# PicoZed.net
KiCad netlist of a schematic drawn in Altium Designer
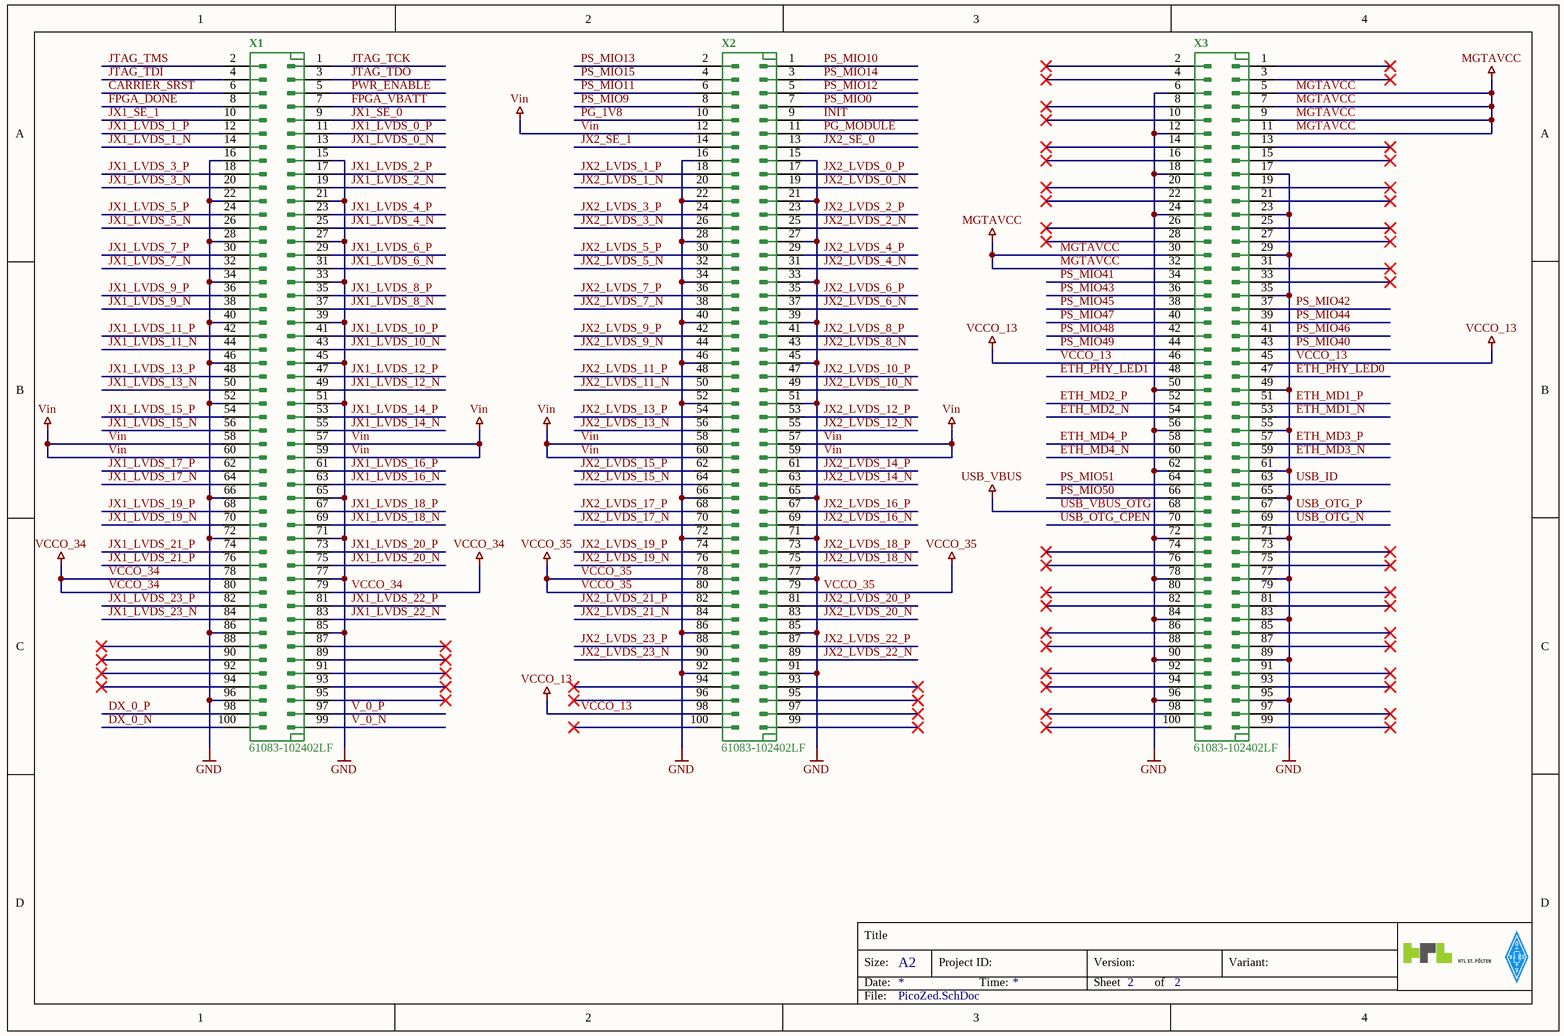
[diagram p0: PicoZed.SchDoc]

(export (version "E")
  (design (tool "Eeschema 10.0.6"))
  (components
    (comp (ref "X1")
      (value "61083-102402LF")
      (footprint "PrometheusLib:61083-102402LF")
      (libsource (lib "PrometheusLib") (part "X_61083-102402LF"))
    )
    (comp (ref "X2")
      (value "61083-102402LF")
      (footprint "PrometheusLib:61083-102402LF")
      (libsource (lib "PrometheusLib") (part "X_61083-102402LF"))
    )
    (comp (ref "X3")
      (value "61083-102402LF")
      (footprint "PrometheusLib:61083-102402LF")
      (libsource (lib "PrometheusLib") (part "X_61083-102402LF"))
    )
  )
  (nets
    (net (code "1") (name "/DX_0_N") (class "Default")
      (node (ref "X1") (pin "100") (pinfunction "100_100") (pintype "passive"))
    )
    (net (code "2") (name "/DX_0_P") (class "Default")
      (node (ref "X1") (pin "98") (pinfunction "98_98") (pintype "passive"))
    )
    (net (code "3") (name "/ETH_MD1_N") (class "Default")
      (node (ref "X3") (pin "53") (pinfunction "53_53") (pintype "passive"))
    )
    (net (code "4") (name "/ETH_MD1_P") (class "Default")
      (node (ref "X3") (pin "51") (pinfunction "51_51") (pintype "passive"))
    )
    (net (code "5") (name "/ETH_MD2_N") (class "Default")
      (node (ref "X3") (pin "54") (pinfunction "54_54") (pintype "passive"))
    )
    (net (code "6") (name "/ETH_MD2_P") (class "Default")
      (node (ref "X3") (pin "52") (pinfunction "52_52") (pintype "passive"))
    )
    (net (code "7") (name "/ETH_MD3_N") (class "Default")
      (node (ref "X3") (pin "59") (pinfunction "59_59") (pintype "passive"))
    )
    (net (code "8") (name "/ETH_MD3_P") (class "Default")
      (node (ref "X3") (pin "57") (pinfunction "57_57") (pintype "passive"))
    )
    (net (code "9") (name "/ETH_MD4_N") (class "Default")
      (node (ref "X3") (pin "60") (pinfunction "60_60") (pintype "passive"))
    )
    (net (code "10") (name "/ETH_MD4_P") (class "Default")
      (node (ref "X3") (pin "58") (pinfunction "58_58") (pintype "passive"))
    )
    (net (code "11") (name "/ETH_PHY_LED0") (class "Default")
      (node (ref "X3") (pin "47") (pinfunction "47_47") (pintype "passive"))
    )
    (net (code "12") (name "/ETH_PHY_LED1") (class "Default")
      (node (ref "X3") (pin "48") (pinfunction "48_48") (pintype "passive"))
    )
    (net (code "13") (name "/FPGA_DONE") (class "Default")
      (node (ref "X1") (pin "8") (pinfunction "8_8") (pintype "passive"))
    )
    (net (code "14") (name "/FPGA_VBATT") (class "Default")
      (node (ref "X1") (pin "7") (pinfunction "7_7") (pintype "passive"))
    )
    (net (code "15") (name "/JTAG_TCK") (class "Default")
      (node (ref "X1") (pin "1") (pinfunction "1_1") (pintype "passive"))
    )
    (net (code "16") (name "/JTAG_TDI") (class "Default")
      (node (ref "X1") (pin "4") (pinfunction "4_4") (pintype "passive"))
    )
    (net (code "17") (name "/JTAG_TDO") (class "Default")
      (node (ref "X1") (pin "3") (pinfunction "3_3") (pintype "passive"))
    )
    (net (code "18") (name "/JTAG_TMS") (class "Default")
      (node (ref "X1") (pin "2") (pinfunction "2_2") (pintype "passive"))
    )
    (net (code "19") (name "/JX1_LVDS_0_N") (class "Default")
      (node (ref "X1") (pin "13") (pinfunction "13_13") (pintype "passive"))
    )
    (net (code "20") (name "/JX1_LVDS_0_P") (class "Default")
      (node (ref "X1") (pin "11") (pinfunction "11_11") (pintype "passive"))
    )
    (net (code "21") (name "/JX1_LVDS_1_N") (class "Default")
      (node (ref "X1") (pin "14") (pinfunction "14_14") (pintype "passive"))
    )
    (net (code "22") (name "/JX1_LVDS_1_P") (class "Default")
      (node (ref "X1") (pin "12") (pinfunction "12_12") (pintype "passive"))
    )
    (net (code "23") (name "/JX1_LVDS_2_N") (class "Default")
      (node (ref "X1") (pin "19") (pinfunction "19_19") (pintype "passive"))
    )
    (net (code "24") (name "/JX1_LVDS_2_P") (class "Default")
      (node (ref "X1") (pin "17") (pinfunction "17_17") (pintype "passive"))
    )
    (net (code "25") (name "/JX1_LVDS_3_N") (class "Default")
      (node (ref "X1") (pin "20") (pinfunction "20_20") (pintype "passive"))
    )
    (net (code "26") (name "/JX1_LVDS_3_P") (class "Default")
      (node (ref "X1") (pin "18") (pinfunction "18_18") (pintype "passive"))
    )
    (net (code "27") (name "/JX1_LVDS_4_N") (class "Default")
      (node (ref "X1") (pin "25") (pinfunction "25_25") (pintype "passive"))
    )
    (net (code "28") (name "/JX1_LVDS_4_P") (class "Default")
      (node (ref "X1") (pin "23") (pinfunction "23_23") (pintype "passive"))
    )
    (net (code "29") (name "/JX1_LVDS_5_N") (class "Default")
      (node (ref "X1") (pin "26") (pinfunction "26_26") (pintype "passive"))
    )
    (net (code "30") (name "/JX1_LVDS_5_P") (class "Default")
      (node (ref "X1") (pin "24") (pinfunction "24_24") (pintype "passive"))
    )
    (net (code "31") (name "/JX1_LVDS_6_N") (class "Default")
      (node (ref "X1") (pin "31") (pinfunction "31_31") (pintype "passive"))
    )
    (net (code "32") (name "/JX1_LVDS_6_P") (class "Default")
      (node (ref "X1") (pin "29") (pinfunction "29_29") (pintype "passive"))
    )
    (net (code "33") (name "/JX1_LVDS_7_N") (class "Default")
      (node (ref "X1") (pin "32") (pinfunction "32_32") (pintype "passive"))
    )
    (net (code "34") (name "/JX1_LVDS_7_P") (class "Default")
      (node (ref "X1") (pin "30") (pinfunction "30_30") (pintype "passive"))
    )
    (net (code "35") (name "/JX1_LVDS_8_N") (class "Default")
      (node (ref "X1") (pin "37") (pinfunction "37_37") (pintype "passive"))
    )
    (net (code "36") (name "/JX1_LVDS_8_P") (class "Default")
      (node (ref "X1") (pin "35") (pinfunction "35_35") (pintype "passive"))
    )
    (net (code "37") (name "/JX1_LVDS_9_N") (class "Default")
      (node (ref "X1") (pin "38") (pinfunction "38_38") (pintype "passive"))
    )
    (net (code "38") (name "/JX1_LVDS_9_P") (class "Default")
      (node (ref "X1") (pin "36") (pinfunction "36_36") (pintype "passive"))
    )
    (net (code "39") (name "/JX1_LVDS_10_N") (class "Default")
      (node (ref "X1") (pin "43") (pinfunction "43_43") (pintype "passive"))
    )
    (net (code "40") (name "/JX1_LVDS_10_P") (class "Default")
      (node (ref "X1") (pin "41") (pinfunction "41_41") (pintype "passive"))
    )
    (net (code "41") (name "/JX1_LVDS_11_N") (class "Default")
      (node (ref "X1") (pin "44") (pinfunction "44_44") (pintype "passive"))
    )
    (net (code "42") (name "/JX1_LVDS_11_P") (class "Default")
      (node (ref "X1") (pin "42") (pinfunction "42_42") (pintype "passive"))
    )
    (net (code "43") (name "/JX1_LVDS_12_N") (class "Default")
      (node (ref "X1") (pin "49") (pinfunction "49_49") (pintype "passive"))
    )
    (net (code "44") (name "/JX1_LVDS_12_P") (class "Default")
      (node (ref "X1") (pin "47") (pinfunction "47_47") (pintype "passive"))
    )
    (net (code "45") (name "/JX1_LVDS_13_N") (class "Default")
      (node (ref "X1") (pin "50") (pinfunction "50_50") (pintype "passive"))
    )
    (net (code "46") (name "/JX1_LVDS_13_P") (class "Default")
      (node (ref "X1") (pin "48") (pinfunction "48_48") (pintype "passive"))
    )
    (net (code "47") (name "/JX1_LVDS_14_N") (class "Default")
      (node (ref "X1") (pin "55") (pinfunction "55_55") (pintype "passive"))
    )
    (net (code "48") (name "/JX1_LVDS_14_P") (class "Default")
      (node (ref "X1") (pin "53") (pinfunction "53_53") (pintype "passive"))
    )
    (net (code "49") (name "/JX1_LVDS_15_N") (class "Default")
      (node (ref "X1") (pin "56") (pinfunction "56_56") (pintype "passive"))
    )
    (net (code "50") (name "/JX1_LVDS_15_P") (class "Default")
      (node (ref "X1") (pin "54") (pinfunction "54_54") (pintype "passive"))
    )
    (net (code "51") (name "/JX1_LVDS_16_N") (class "Default")
      (node (ref "X1") (pin "63") (pinfunction "63_63") (pintype "passive"))
    )
    (net (code "52") (name "/JX1_LVDS_16_P") (class "Default")
      (node (ref "X1") (pin "61") (pinfunction "61_61") (pintype "passive"))
    )
    (net (code "53") (name "/JX1_LVDS_17_N") (class "Default")
      (node (ref "X1") (pin "64") (pinfunction "64_64") (pintype "passive"))
    )
    (net (code "54") (name "/JX1_LVDS_17_P") (class "Default")
      (node (ref "X1") (pin "62") (pinfunction "62_62") (pintype "passive"))
    )
    (net (code "55") (name "/JX1_LVDS_18_N") (class "Default")
      (node (ref "X1") (pin "69") (pinfunction "69_69") (pintype "passive"))
    )
    (net (code "56") (name "/JX1_LVDS_18_P") (class "Default")
      (node (ref "X1") (pin "67") (pinfunction "67_67") (pintype "passive"))
    )
    (net (code "57") (name "/JX1_LVDS_19_N") (class "Default")
      (node (ref "X1") (pin "70") (pinfunction "70_70") (pintype "passive"))
    )
    (net (code "58") (name "/JX1_LVDS_19_P") (class "Default")
      (node (ref "X1") (pin "68") (pinfunction "68_68") (pintype "passive"))
    )
    (net (code "59") (name "/JX1_LVDS_20_N") (class "Default")
      (node (ref "X1") (pin "75") (pinfunction "75_75") (pintype "passive"))
    )
    (net (code "60") (name "/JX1_LVDS_20_P") (class "Default")
      (node (ref "X1") (pin "73") (pinfunction "73_73") (pintype "passive"))
    )
    (net (code "61") (name "/JX1_LVDS_21_P") (class "Default")
      (node (ref "X1") (pin "74") (pinfunction "74_74") (pintype "passive"))
      (node (ref "X1") (pin "76") (pinfunction "76_76") (pintype "passive"))
    )
    (net (code "62") (name "/JX1_LVDS_22_N") (class "Default")
      (node (ref "X1") (pin "83") (pinfunction "83_83") (pintype "passive"))
    )
    (net (code "63") (name "/JX1_LVDS_22_P") (class "Default")
      (node (ref "X1") (pin "81") (pinfunction "81_81") (pintype "passive"))
    )
    (net (code "64") (name "/JX1_LVDS_23_N") (class "Default")
      (node (ref "X1") (pin "84") (pinfunction "84_84") (pintype "passive"))
    )
    (net (code "65") (name "/JX1_LVDS_23_P") (class "Default")
      (node (ref "X1") (pin "82") (pinfunction "82_82") (pintype "passive"))
    )
    (net (code "66") (name "/JX1_SE_0") (class "Default")
      (node (ref "X1") (pin "9") (pinfunction "9_9") (pintype "passive"))
    )
    (net (code "67") (name "/JX1_SE_1") (class "Default")
      (node (ref "X1") (pin "10") (pinfunction "10_10") (pintype "passive"))
    )
    (net (code "68") (name "/JX2_LVDS_0_N") (class "Default")
      (node (ref "X2") (pin "19") (pinfunction "19_19") (pintype "passive"))
    )
    (net (code "69") (name "/JX2_LVDS_0_P") (class "Default")
      (node (ref "X2") (pin "17") (pinfunction "17_17") (pintype "passive"))
    )
    (net (code "70") (name "/JX2_LVDS_1_N") (class "Default")
      (node (ref "X2") (pin "20") (pinfunction "20_20") (pintype "passive"))
    )
    (net (code "71") (name "/JX2_LVDS_1_P") (class "Default")
      (node (ref "X2") (pin "18") (pinfunction "18_18") (pintype "passive"))
    )
    (net (code "72") (name "/JX2_LVDS_2_N") (class "Default")
      (node (ref "X2") (pin "25") (pinfunction "25_25") (pintype "passive"))
    )
    (net (code "73") (name "/JX2_LVDS_2_P") (class "Default")
      (node (ref "X2") (pin "23") (pinfunction "23_23") (pintype "passive"))
    )
    (net (code "74") (name "/JX2_LVDS_3_N") (class "Default")
      (node (ref "X2") (pin "26") (pinfunction "26_26") (pintype "passive"))
    )
    (net (code "75") (name "/JX2_LVDS_3_P") (class "Default")
      (node (ref "X2") (pin "24") (pinfunction "24_24") (pintype "passive"))
    )
    (net (code "76") (name "/JX2_LVDS_4_N") (class "Default")
      (node (ref "X2") (pin "31") (pinfunction "31_31") (pintype "passive"))
    )
    (net (code "77") (name "/JX2_LVDS_4_P") (class "Default")
      (node (ref "X2") (pin "29") (pinfunction "29_29") (pintype "passive"))
    )
    (net (code "78") (name "/JX2_LVDS_5_N") (class "Default")
      (node (ref "X2") (pin "32") (pinfunction "32_32") (pintype "passive"))
    )
    (net (code "79") (name "/JX2_LVDS_5_P") (class "Default")
      (node (ref "X2") (pin "30") (pinfunction "30_30") (pintype "passive"))
    )
    (net (code "80") (name "/JX2_LVDS_6_N") (class "Default")
      (node (ref "X2") (pin "37") (pinfunction "37_37") (pintype "passive"))
    )
    (net (code "81") (name "/JX2_LVDS_6_P") (class "Default")
      (node (ref "X2") (pin "35") (pinfunction "35_35") (pintype "passive"))
    )
    (net (code "82") (name "/JX2_LVDS_7_N") (class "Default")
      (node (ref "X2") (pin "38") (pinfunction "38_38") (pintype "passive"))
    )
    (net (code "83") (name "/JX2_LVDS_7_P") (class "Default")
      (node (ref "X2") (pin "36") (pinfunction "36_36") (pintype "passive"))
    )
    (net (code "84") (name "/JX2_LVDS_8_N") (class "Default")
      (node (ref "X2") (pin "43") (pinfunction "43_43") (pintype "passive"))
    )
    (net (code "85") (name "/JX2_LVDS_8_P") (class "Default")
      (node (ref "X2") (pin "41") (pinfunction "41_41") (pintype "passive"))
    )
    (net (code "86") (name "/JX2_LVDS_9_N") (class "Default")
      (node (ref "X2") (pin "44") (pinfunction "44_44") (pintype "passive"))
    )
    (net (code "87") (name "/JX2_LVDS_9_P") (class "Default")
      (node (ref "X2") (pin "42") (pinfunction "42_42") (pintype "passive"))
    )
    (net (code "88") (name "/JX2_LVDS_10_N") (class "Default")
      (node (ref "X2") (pin "49") (pinfunction "49_49") (pintype "passive"))
    )
    (net (code "89") (name "/JX2_LVDS_10_P") (class "Default")
      (node (ref "X2") (pin "47") (pinfunction "47_47") (pintype "passive"))
    )
    (net (code "90") (name "/JX2_LVDS_11_N") (class "Default")
      (node (ref "X2") (pin "50") (pinfunction "50_50") (pintype "passive"))
    )
    (net (code "91") (name "/JX2_LVDS_11_P") (class "Default")
      (node (ref "X2") (pin "48") (pinfunction "48_48") (pintype "passive"))
    )
    (net (code "92") (name "/JX2_LVDS_12_N") (class "Default")
      (node (ref "X2") (pin "55") (pinfunction "55_55") (pintype "passive"))
    )
    (net (code "93") (name "/JX2_LVDS_12_P") (class "Default")
      (node (ref "X2") (pin "53") (pinfunction "53_53") (pintype "passive"))
    )
    (net (code "94") (name "/JX2_LVDS_13_N") (class "Default")
      (node (ref "X2") (pin "56") (pinfunction "56_56") (pintype "passive"))
    )
    (net (code "95") (name "/JX2_LVDS_13_P") (class "Default")
      (node (ref "X2") (pin "54") (pinfunction "54_54") (pintype "passive"))
    )
    (net (code "96") (name "/JX2_LVDS_14_N") (class "Default")
      (node (ref "X2") (pin "63") (pinfunction "63_63") (pintype "passive"))
    )
    (net (code "97") (name "/JX2_LVDS_14_P") (class "Default")
      (node (ref "X2") (pin "61") (pinfunction "61_61") (pintype "passive"))
    )
    (net (code "98") (name "/JX2_LVDS_15_N") (class "Default")
      (node (ref "X2") (pin "64") (pinfunction "64_64") (pintype "passive"))
    )
    (net (code "99") (name "/JX2_LVDS_15_P") (class "Default")
      (node (ref "X2") (pin "62") (pinfunction "62_62") (pintype "passive"))
    )
    (net (code "100") (name "/JX2_LVDS_16_N") (class "Default")
      (node (ref "X2") (pin "69") (pinfunction "69_69") (pintype "passive"))
    )
    (net (code "101") (name "/JX2_LVDS_16_P") (class "Default")
      (node (ref "X2") (pin "67") (pinfunction "67_67") (pintype "passive"))
    )
    (net (code "102") (name "/JX2_LVDS_17_N") (class "Default")
      (node (ref "X2") (pin "70") (pinfunction "70_70") (pintype "passive"))
    )
    (net (code "103") (name "/JX2_LVDS_17_P") (class "Default")
      (node (ref "X2") (pin "68") (pinfunction "68_68") (pintype "passive"))
    )
    (net (code "104") (name "/JX2_LVDS_18_N") (class "Default")
      (node (ref "X2") (pin "75") (pinfunction "75_75") (pintype "passive"))
    )
    (net (code "105") (name "/JX2_LVDS_18_P") (class "Default")
      (node (ref "X2") (pin "73") (pinfunction "73_73") (pintype "passive"))
    )
    (net (code "106") (name "/JX2_LVDS_19_N") (class "Default")
      (node (ref "X2") (pin "76") (pinfunction "76_76") (pintype "passive"))
    )
    (net (code "107") (name "/JX2_LVDS_19_P") (class "Default")
      (node (ref "X2") (pin "74") (pinfunction "74_74") (pintype "passive"))
    )
    (net (code "108") (name "/JX2_LVDS_20_N") (class "Default")
      (node (ref "X2") (pin "83") (pinfunction "83_83") (pintype "passive"))
    )
    (net (code "109") (name "/JX2_LVDS_20_P") (class "Default")
      (node (ref "X2") (pin "81") (pinfunction "81_81") (pintype "passive"))
    )
    (net (code "110") (name "/JX2_LVDS_21_N") (class "Default")
      (node (ref "X2") (pin "84") (pinfunction "84_84") (pintype "passive"))
    )
    (net (code "111") (name "/JX2_LVDS_21_P") (class "Default")
      (node (ref "X2") (pin "82") (pinfunction "82_82") (pintype "passive"))
    )
    (net (code "112") (name "/JX2_LVDS_22_N") (class "Default")
      (node (ref "X2") (pin "89") (pinfunction "89_89") (pintype "passive"))
    )
    (net (code "113") (name "/JX2_LVDS_22_P") (class "Default")
      (node (ref "X2") (pin "87") (pinfunction "87_87") (pintype "passive"))
    )
    (net (code "114") (name "/JX2_LVDS_23_N") (class "Default")
      (node (ref "X2") (pin "90") (pinfunction "90_90") (pintype "passive"))
    )
    (net (code "115") (name "/JX2_LVDS_23_P") (class "Default")
      (node (ref "X2") (pin "88") (pinfunction "88_88") (pintype "passive"))
    )
    (net (code "116") (name "/JX2_SE_0") (class "Default")
      (node (ref "X2") (pin "13") (pinfunction "13_13") (pintype "passive"))
    )
    (net (code "117") (name "/JX2_SE_1") (class "Default")
      (node (ref "X2") (pin "14") (pinfunction "14_14") (pintype "passive"))
    )
    (net (code "118") (name "/PG_1V8") (class "Default")
      (node (ref "X2") (pin "10") (pinfunction "10_10") (pintype "passive"))
    )
    (net (code "119") (name "/PG_MODULE") (class "Default")
      (node (ref "X2") (pin "11") (pinfunction "11_11") (pintype "passive"))
    )
    (net (code "120") (name "/PS_MIO0") (class "Default")
      (node (ref "X2") (pin "7") (pinfunction "7_7") (pintype "passive"))
    )
    (net (code "121") (name "/PS_MIO9") (class "Default")
      (node (ref "X2") (pin "8") (pinfunction "8_8") (pintype "passive"))
    )
    (net (code "122") (name "/PS_MIO10") (class "Default")
      (node (ref "X2") (pin "1") (pinfunction "1_1") (pintype "passive"))
    )
    (net (code "123") (name "/PS_MIO11") (class "Default")
      (node (ref "X2") (pin "6") (pinfunction "6_6") (pintype "passive"))
    )
    (net (code "124") (name "/PS_MIO12") (class "Default")
      (node (ref "X2") (pin "5") (pinfunction "5_5") (pintype "passive"))
    )
    (net (code "125") (name "/PS_MIO13") (class "Default")
      (node (ref "X2") (pin "2") (pinfunction "2_2") (pintype "passive"))
    )
    (net (code "126") (name "/PS_MIO14") (class "Default")
      (node (ref "X2") (pin "3") (pinfunction "3_3") (pintype "passive"))
    )
    (net (code "127") (name "/PS_MIO15") (class "Default")
      (node (ref "X2") (pin "4") (pinfunction "4_4") (pintype "passive"))
    )
    (net (code "128") (name "/PS_MIO40") (class "Default")
      (node (ref "X3") (pin "43") (pinfunction "43_43") (pintype "passive"))
    )
    (net (code "129") (name "/PS_MIO41") (class "Default")
      (node (ref "X3") (pin "34") (pinfunction "34_34") (pintype "passive"))
    )
    (net (code "130") (name "/PS_MIO42") (class "Default")
      (node (ref "X3") (pin "37") (pinfunction "37_37") (pintype "passive"))
    )
    (net (code "131") (name "/PS_MIO43") (class "Default")
      (node (ref "X3") (pin "36") (pinfunction "36_36") (pintype "passive"))
    )
    (net (code "132") (name "/PS_MIO44") (class "Default")
      (node (ref "X3") (pin "39") (pinfunction "39_39") (pintype "passive"))
    )
    (net (code "133") (name "/PS_MIO45") (class "Default")
      (node (ref "X3") (pin "38") (pinfunction "38_38") (pintype "passive"))
    )
    (net (code "134") (name "/PS_MIO46") (class "Default")
      (node (ref "X3") (pin "41") (pinfunction "41_41") (pintype "passive"))
    )
    (net (code "135") (name "/PS_MIO47") (class "Default")
      (node (ref "X3") (pin "40") (pinfunction "40_40") (pintype "passive"))
    )
    (net (code "136") (name "/PS_MIO48") (class "Default")
      (node (ref "X3") (pin "42") (pinfunction "42_42") (pintype "passive"))
    )
    (net (code "137") (name "/PS_MIO49") (class "Default")
      (node (ref "X3") (pin "44") (pinfunction "44_44") (pintype "passive"))
    )
    (net (code "138") (name "/PS_MIO50") (class "Default")
      (node (ref "X3") (pin "66") (pinfunction "66_66") (pintype "passive"))
    )
    (net (code "139") (name "/PS_MIO51") (class "Default")
      (node (ref "X3") (pin "64") (pinfunction "64_64") (pintype "passive"))
    )
    (net (code "140") (name "/PWR_ENABLE") (class "Default")
      (node (ref "X1") (pin "5") (pinfunction "5_5") (pintype "passive"))
    )
    (net (code "141") (name "/USB_ID") (class "Default")
      (node (ref "X3") (pin "63") (pinfunction "63_63") (pintype "passive"))
    )
    (net (code "142") (name "/USB_OTG_CPEN") (class "Default")
      (node (ref "X3") (pin "70") (pinfunction "70_70") (pintype "passive"))
    )
    (net (code "143") (name "/USB_OTG_N") (class "Default")
      (node (ref "X3") (pin "69") (pinfunction "69_69") (pintype "passive"))
    )
    (net (code "144") (name "/USB_OTG_P") (class "Default")
      (node (ref "X3") (pin "67") (pinfunction "67_67") (pintype "passive"))
    )
    (net (code "145") (name "/V_0_N") (class "Default")
      (node (ref "X1") (pin "99") (pinfunction "99_99") (pintype "passive"))
    )
    (net (code "146") (name "/V_0_P") (class "Default")
      (node (ref "X1") (pin "97") (pinfunction "97_97") (pintype "passive"))
    )
    (net (code "147") (name "/~{CARRIER_SRS}T") (class "Default")
      (node (ref "X1") (pin "6") (pinfunction "6_6") (pintype "passive"))
    )
    (net (code "148") (name "/~{INI}T") (class "Default")
      (node (ref "X2") (pin "9") (pinfunction "9_9") (pintype "passive"))
    )
    (net (code "149") (name "GND") (class "Default")
      (node (ref "X1") (pin "15") (pinfunction "15_15") (pintype "passive"))
      (node (ref "X1") (pin "16") (pinfunction "16_16") (pintype "passive"))
      (node (ref "X1") (pin "21") (pinfunction "21_21") (pintype "passive"))
      (node (ref "X1") (pin "22") (pinfunction "22_22") (pintype "passive"))
      (node (ref "X1") (pin "27") (pinfunction "27_27") (pintype "passive"))
      (node (ref "X1") (pin "28") (pinfunction "28_28") (pintype "passive"))
      (node (ref "X1") (pin "33") (pinfunction "33_33") (pintype "passive"))
      (node (ref "X1") (pin "34") (pinfunction "34_34") (pintype "passive"))
      (node (ref "X1") (pin "39") (pinfunction "39_39") (pintype "passive"))
      (node (ref "X1") (pin "40") (pinfunction "40_40") (pintype "passive"))
      (node (ref "X1") (pin "45") (pinfunction "45_45") (pintype "passive"))
      (node (ref "X1") (pin "46") (pinfunction "46_46") (pintype "passive"))
      (node (ref "X1") (pin "51") (pinfunction "51_51") (pintype "passive"))
      (node (ref "X1") (pin "52") (pinfunction "52_52") (pintype "passive"))
      (node (ref "X1") (pin "65") (pinfunction "65_65") (pintype "passive"))
      (node (ref "X1") (pin "66") (pinfunction "66_66") (pintype "passive"))
      (node (ref "X1") (pin "71") (pinfunction "71_71") (pintype "passive"))
      (node (ref "X1") (pin "72") (pinfunction "72_72") (pintype "passive"))
      (node (ref "X1") (pin "77") (pinfunction "77_77") (pintype "passive"))
      (node (ref "X1") (pin "85") (pinfunction "85_85") (pintype "passive"))
      (node (ref "X1") (pin "86") (pinfunction "86_86") (pintype "passive"))
      (node (ref "X1") (pin "96") (pinfunction "96_96") (pintype "passive"))
      (node (ref "X2") (pin "15") (pinfunction "15_15") (pintype "passive"))
      (node (ref "X2") (pin "16") (pinfunction "16_16") (pintype "passive"))
      (node (ref "X2") (pin "21") (pinfunction "21_21") (pintype "passive"))
      (node (ref "X2") (pin "22") (pinfunction "22_22") (pintype "passive"))
      (node (ref "X2") (pin "27") (pinfunction "27_27") (pintype "passive"))
      (node (ref "X2") (pin "28") (pinfunction "28_28") (pintype "passive"))
      (node (ref "X2") (pin "33") (pinfunction "33_33") (pintype "passive"))
      (node (ref "X2") (pin "34") (pinfunction "34_34") (pintype "passive"))
      (node (ref "X2") (pin "39") (pinfunction "39_39") (pintype "passive"))
      (node (ref "X2") (pin "40") (pinfunction "40_40") (pintype "passive"))
      (node (ref "X2") (pin "45") (pinfunction "45_45") (pintype "passive"))
      (node (ref "X2") (pin "46") (pinfunction "46_46") (pintype "passive"))
      (node (ref "X2") (pin "51") (pinfunction "51_51") (pintype "passive"))
      (node (ref "X2") (pin "52") (pinfunction "52_52") (pintype "passive"))
      (node (ref "X2") (pin "65") (pinfunction "65_65") (pintype "passive"))
      (node (ref "X2") (pin "66") (pinfunction "66_66") (pintype "passive"))
      (node (ref "X2") (pin "71") (pinfunction "71_71") (pintype "passive"))
      (node (ref "X2") (pin "72") (pinfunction "72_72") (pintype "passive"))
      (node (ref "X2") (pin "77") (pinfunction "77_77") (pintype "passive"))
      (node (ref "X2") (pin "85") (pinfunction "85_85") (pintype "passive"))
      (node (ref "X2") (pin "86") (pinfunction "86_86") (pintype "passive"))
      (node (ref "X2") (pin "91") (pinfunction "91_91") (pintype "passive"))
      (node (ref "X2") (pin "92") (pinfunction "92_92") (pintype "passive"))
      (node (ref "X3") (pin "12") (pinfunction "12_12") (pintype "passive"))
      (node (ref "X3") (pin "17") (pinfunction "17_17") (pintype "passive"))
      (node (ref "X3") (pin "18") (pinfunction "18_18") (pintype "passive"))
      (node (ref "X3") (pin "23") (pinfunction "23_23") (pintype "passive"))
      (node (ref "X3") (pin "24") (pinfunction "24_24") (pintype "passive"))
      (node (ref "X3") (pin "29") (pinfunction "29_29") (pintype "passive"))
      (node (ref "X3") (pin "35") (pinfunction "35_35") (pintype "passive"))
      (node (ref "X3") (pin "49") (pinfunction "49_49") (pintype "passive"))
      (node (ref "X3") (pin "50") (pinfunction "50_50") (pintype "passive"))
      (node (ref "X3") (pin "55") (pinfunction "55_55") (pintype "passive"))
      (node (ref "X3") (pin "56") (pinfunction "56_56") (pintype "passive"))
      (node (ref "X3") (pin "6") (pinfunction "6_6") (pintype "passive"))
      (node (ref "X3") (pin "61") (pinfunction "61_61") (pintype "passive"))
      (node (ref "X3") (pin "62") (pinfunction "62_62") (pintype "passive"))
      (node (ref "X3") (pin "65") (pinfunction "65_65") (pintype "passive"))
      (node (ref "X3") (pin "71") (pinfunction "71_71") (pintype "passive"))
      (node (ref "X3") (pin "72") (pinfunction "72_72") (pintype "passive"))
      (node (ref "X3") (pin "77") (pinfunction "77_77") (pintype "passive"))
      (node (ref "X3") (pin "78") (pinfunction "78_78") (pintype "passive"))
      (node (ref "X3") (pin "83") (pinfunction "83_83") (pintype "passive"))
      (node (ref "X3") (pin "84") (pinfunction "84_84") (pintype "passive"))
      (node (ref "X3") (pin "89") (pinfunction "89_89") (pintype "passive"))
      (node (ref "X3") (pin "90") (pinfunction "90_90") (pintype "passive"))
      (node (ref "X3") (pin "95") (pinfunction "95_95") (pintype "passive"))
      (node (ref "X3") (pin "96") (pinfunction "96_96") (pintype "passive"))
    )
    (net (code "150") (name "MGTAVCC") (class "Default")
      (node (ref "X3") (pin "11") (pinfunction "11_11") (pintype "passive"))
      (node (ref "X3") (pin "30") (pinfunction "30_30") (pintype "passive"))
      (node (ref "X3") (pin "32") (pinfunction "32_32") (pintype "passive"))
      (node (ref "X3") (pin "5") (pinfunction "5_5") (pintype "passive"))
      (node (ref "X3") (pin "7") (pinfunction "7_7") (pintype "passive"))
      (node (ref "X3") (pin "9") (pinfunction "9_9") (pintype "passive"))
    )
    (net (code "151") (name "USB_VBUS") (class "Default")
      (node (ref "X3") (pin "68") (pinfunction "68_68") (pintype "passive"))
    )
    (net (code "152") (name "VCCO_13") (class "Default")
      (node (ref "X2") (pin "98") (pinfunction "98_98") (pintype "passive"))
      (node (ref "X3") (pin "45") (pinfunction "45_45") (pintype "passive"))
      (node (ref "X3") (pin "46") (pinfunction "46_46") (pintype "passive"))
    )
    (net (code "153") (name "VCCO_34") (class "Default")
      (node (ref "X1") (pin "78") (pinfunction "78_78") (pintype "passive"))
      (node (ref "X1") (pin "79") (pinfunction "79_79") (pintype "passive"))
      (node (ref "X1") (pin "80") (pinfunction "80_80") (pintype "passive"))
    )
    (net (code "154") (name "VCCO_35") (class "Default")
      (node (ref "X2") (pin "78") (pinfunction "78_78") (pintype "passive"))
      (node (ref "X2") (pin "79") (pinfunction "79_79") (pintype "passive"))
      (node (ref "X2") (pin "80") (pinfunction "80_80") (pintype "passive"))
    )
    (net (code "155") (name "Vin") (class "Default")
      (node (ref "X1") (pin "57") (pinfunction "57_57") (pintype "passive"))
      (node (ref "X1") (pin "58") (pinfunction "58_58") (pintype "passive"))
      (node (ref "X1") (pin "59") (pinfunction "59_59") (pintype "passive"))
      (node (ref "X1") (pin "60") (pinfunction "60_60") (pintype "passive"))
      (node (ref "X2") (pin "12") (pinfunction "12_12") (pintype "passive"))
      (node (ref "X2") (pin "57") (pinfunction "57_57") (pintype "passive"))
      (node (ref "X2") (pin "58") (pinfunction "58_58") (pintype "passive"))
      (node (ref "X2") (pin "59") (pinfunction "59_59") (pintype "passive"))
      (node (ref "X2") (pin "60") (pinfunction "60_60") (pintype "passive"))
    )
    (net (code "156") (name "unconnected-(X1-Pad87)") (class "Default")
      (node (ref "X1") (pin "87") (pinfunction "87_87") (pintype "passive+no_connect"))
    )
    (net (code "157") (name "unconnected-(X1-Pad88)") (class "Default")
      (node (ref "X1") (pin "88") (pinfunction "88_88") (pintype "passive+no_connect"))
    )
    (net (code "158") (name "unconnected-(X1-Pad89)") (class "Default")
      (node (ref "X1") (pin "89") (pinfunction "89_89") (pintype "passive+no_connect"))
    )
    (net (code "159") (name "unconnected-(X1-Pad90)") (class "Default")
      (node (ref "X1") (pin "90") (pinfunction "90_90") (pintype "passive+no_connect"))
    )
    (net (code "160") (name "unconnected-(X1-Pad91)") (class "Default")
      (node (ref "X1") (pin "91") (pinfunction "91_91") (pintype "passive+no_connect"))
    )
    (net (code "161") (name "unconnected-(X1-Pad92)") (class "Default")
      (node (ref "X1") (pin "92") (pinfunction "92_92") (pintype "passive+no_connect"))
    )
    (net (code "162") (name "unconnected-(X1-Pad93)") (class "Default")
      (node (ref "X1") (pin "93") (pinfunction "93_93") (pintype "passive+no_connect"))
    )
    (net (code "163") (name "unconnected-(X1-Pad94)") (class "Default")
      (node (ref "X1") (pin "94") (pinfunction "94_94") (pintype "passive+no_connect"))
    )
    (net (code "164") (name "unconnected-(X1-Pad95)") (class "Default")
      (node (ref "X1") (pin "95") (pinfunction "95_95") (pintype "passive+no_connect"))
    )
    (net (code "165") (name "unconnected-(X2-Pad93)") (class "Default")
      (node (ref "X2") (pin "93") (pinfunction "93_93") (pintype "passive+no_connect"))
    )
    (net (code "166") (name "unconnected-(X2-Pad94)") (class "Default")
      (node (ref "X2") (pin "94") (pinfunction "94_94") (pintype "passive+no_connect"))
    )
    (net (code "167") (name "unconnected-(X2-Pad95)") (class "Default")
      (node (ref "X2") (pin "95") (pinfunction "95_95") (pintype "passive+no_connect"))
    )
    (net (code "168") (name "unconnected-(X2-Pad96)") (class "Default")
      (node (ref "X2") (pin "96") (pinfunction "96_96") (pintype "passive+no_connect"))
    )
    (net (code "169") (name "unconnected-(X2-Pad97)") (class "Default")
      (node (ref "X2") (pin "97") (pinfunction "97_97") (pintype "passive+no_connect"))
    )
    (net (code "170") (name "unconnected-(X2-Pad99)") (class "Default")
      (node (ref "X2") (pin "99") (pinfunction "99_99") (pintype "passive+no_connect"))
    )
    (net (code "171") (name "unconnected-(X2-Pad100)") (class "Default")
      (node (ref "X2") (pin "100") (pinfunction "100_100") (pintype "passive+no_connect"))
    )
    (net (code "172") (name "unconnected-(X3-Pad1)") (class "Default")
      (node (ref "X3") (pin "1") (pinfunction "1_1") (pintype "passive+no_connect"))
    )
    (net (code "173") (name "unconnected-(X3-Pad2)") (class "Default")
      (node (ref "X3") (pin "2") (pinfunction "2_2") (pintype "passive+no_connect"))
    )
    (net (code "174") (name "unconnected-(X3-Pad3)") (class "Default")
      (node (ref "X3") (pin "3") (pinfunction "3_3") (pintype "passive+no_connect"))
    )
    (net (code "175") (name "unconnected-(X3-Pad4)") (class "Default")
      (node (ref "X3") (pin "4") (pinfunction "4_4") (pintype "passive+no_connect"))
    )
    (net (code "176") (name "unconnected-(X3-Pad8)") (class "Default")
      (node (ref "X3") (pin "8") (pinfunction "8_8") (pintype "passive+no_connect"))
    )
    (net (code "177") (name "unconnected-(X3-Pad10)") (class "Default")
      (node (ref "X3") (pin "10") (pinfunction "10_10") (pintype "passive+no_connect"))
    )
    (net (code "178") (name "unconnected-(X3-Pad13)") (class "Default")
      (node (ref "X3") (pin "13") (pinfunction "13_13") (pintype "passive+no_connect"))
    )
    (net (code "179") (name "unconnected-(X3-Pad14)") (class "Default")
      (node (ref "X3") (pin "14") (pinfunction "14_14") (pintype "passive+no_connect"))
    )
    (net (code "180") (name "unconnected-(X3-Pad15)") (class "Default")
      (node (ref "X3") (pin "15") (pinfunction "15_15") (pintype "passive+no_connect"))
    )
    (net (code "181") (name "unconnected-(X3-Pad16)") (class "Default")
      (node (ref "X3") (pin "16") (pinfunction "16_16") (pintype "passive+no_connect"))
    )
    (net (code "182") (name "unconnected-(X3-Pad19)") (class "Default")
      (node (ref "X3") (pin "19") (pinfunction "19_19") (pintype "passive+no_connect"))
    )
    (net (code "183") (name "unconnected-(X3-Pad20)") (class "Default")
      (node (ref "X3") (pin "20") (pinfunction "20_20") (pintype "passive+no_connect"))
    )
    (net (code "184") (name "unconnected-(X3-Pad21)") (class "Default")
      (node (ref "X3") (pin "21") (pinfunction "21_21") (pintype "passive+no_connect"))
    )
    (net (code "185") (name "unconnected-(X3-Pad22)") (class "Default")
      (node (ref "X3") (pin "22") (pinfunction "22_22") (pintype "passive+no_connect"))
    )
    (net (code "186") (name "unconnected-(X3-Pad25)") (class "Default")
      (node (ref "X3") (pin "25") (pinfunction "25_25") (pintype "passive+no_connect"))
    )
    (net (code "187") (name "unconnected-(X3-Pad26)") (class "Default")
      (node (ref "X3") (pin "26") (pinfunction "26_26") (pintype "passive+no_connect"))
    )
    (net (code "188") (name "unconnected-(X3-Pad27)") (class "Default")
      (node (ref "X3") (pin "27") (pinfunction "27_27") (pintype "passive+no_connect"))
    )
    (net (code "189") (name "unconnected-(X3-Pad28)") (class "Default")
      (node (ref "X3") (pin "28") (pinfunction "28_28") (pintype "passive+no_connect"))
    )
    (net (code "190") (name "unconnected-(X3-Pad31)") (class "Default")
      (node (ref "X3") (pin "31") (pinfunction "31_31") (pintype "passive+no_connect"))
    )
    (net (code "191") (name "unconnected-(X3-Pad33)") (class "Default")
      (node (ref "X3") (pin "33") (pinfunction "33_33") (pintype "passive+no_connect"))
    )
    (net (code "192") (name "unconnected-(X3-Pad73)") (class "Default")
      (node (ref "X3") (pin "73") (pinfunction "73_73") (pintype "passive+no_connect"))
    )
    (net (code "193") (name "unconnected-(X3-Pad74)") (class "Default")
      (node (ref "X3") (pin "74") (pinfunction "74_74") (pintype "passive+no_connect"))
    )
    (net (code "194") (name "unconnected-(X3-Pad75)") (class "Default")
      (node (ref "X3") (pin "75") (pinfunction "75_75") (pintype "passive+no_connect"))
    )
    (net (code "195") (name "unconnected-(X3-Pad76)") (class "Default")
      (node (ref "X3") (pin "76") (pinfunction "76_76") (pintype "passive+no_connect"))
    )
    (net (code "196") (name "unconnected-(X3-Pad79)") (class "Default")
      (node (ref "X3") (pin "79") (pinfunction "79_79") (pintype "passive+no_connect"))
    )
    (net (code "197") (name "unconnected-(X3-Pad80)") (class "Default")
      (node (ref "X3") (pin "80") (pinfunction "80_80") (pintype "passive+no_connect"))
    )
    (net (code "198") (name "unconnected-(X3-Pad81)") (class "Default")
      (node (ref "X3") (pin "81") (pinfunction "81_81") (pintype "passive+no_connect"))
    )
    (net (code "199") (name "unconnected-(X3-Pad82)") (class "Default")
      (node (ref "X3") (pin "82") (pinfunction "82_82") (pintype "passive+no_connect"))
    )
    (net (code "200") (name "unconnected-(X3-Pad85)") (class "Default")
      (node (ref "X3") (pin "85") (pinfunction "85_85") (pintype "passive+no_connect"))
    )
    (net (code "201") (name "unconnected-(X3-Pad86)") (class "Default")
      (node (ref "X3") (pin "86") (pinfunction "86_86") (pintype "passive+no_connect"))
    )
    (net (code "202") (name "unconnected-(X3-Pad87)") (class "Default")
      (node (ref "X3") (pin "87") (pinfunction "87_87") (pintype "passive+no_connect"))
    )
    (net (code "203") (name "unconnected-(X3-Pad88)") (class "Default")
      (node (ref "X3") (pin "88") (pinfunction "88_88") (pintype "passive+no_connect"))
    )
    (net (code "204") (name "unconnected-(X3-Pad91)") (class "Default")
      (node (ref "X3") (pin "91") (pinfunction "91_91") (pintype "passive+no_connect"))
    )
    (net (code "205") (name "unconnected-(X3-Pad92)") (class "Default")
      (node (ref "X3") (pin "92") (pinfunction "92_92") (pintype "passive+no_connect"))
    )
    (net (code "206") (name "unconnected-(X3-Pad93)") (class "Default")
      (node (ref "X3") (pin "93") (pinfunction "93_93") (pintype "passive+no_connect"))
    )
    (net (code "207") (name "unconnected-(X3-Pad94)") (class "Default")
      (node (ref "X3") (pin "94") (pinfunction "94_94") (pintype "passive+no_connect"))
    )
    (net (code "208") (name "unconnected-(X3-Pad97)") (class "Default")
      (node (ref "X3") (pin "97") (pinfunction "97_97") (pintype "passive+no_connect"))
    )
    (net (code "209") (name "unconnected-(X3-Pad98)") (class "Default")
      (node (ref "X3") (pin "98") (pinfunction "98_98") (pintype "passive+no_connect"))
    )
    (net (code "210") (name "unconnected-(X3-Pad99)") (class "Default")
      (node (ref "X3") (pin "99") (pinfunction "99_99") (pintype "passive+no_connect"))
    )
    (net (code "211") (name "unconnected-(X3-Pad100)") (class "Default")
      (node (ref "X3") (pin "100") (pinfunction "100_100") (pintype "passive+no_connect"))
    )
  )
)
